# CH32V467WEU-R0.net
KiCad netlist of a schematic drawn in Altium Designer
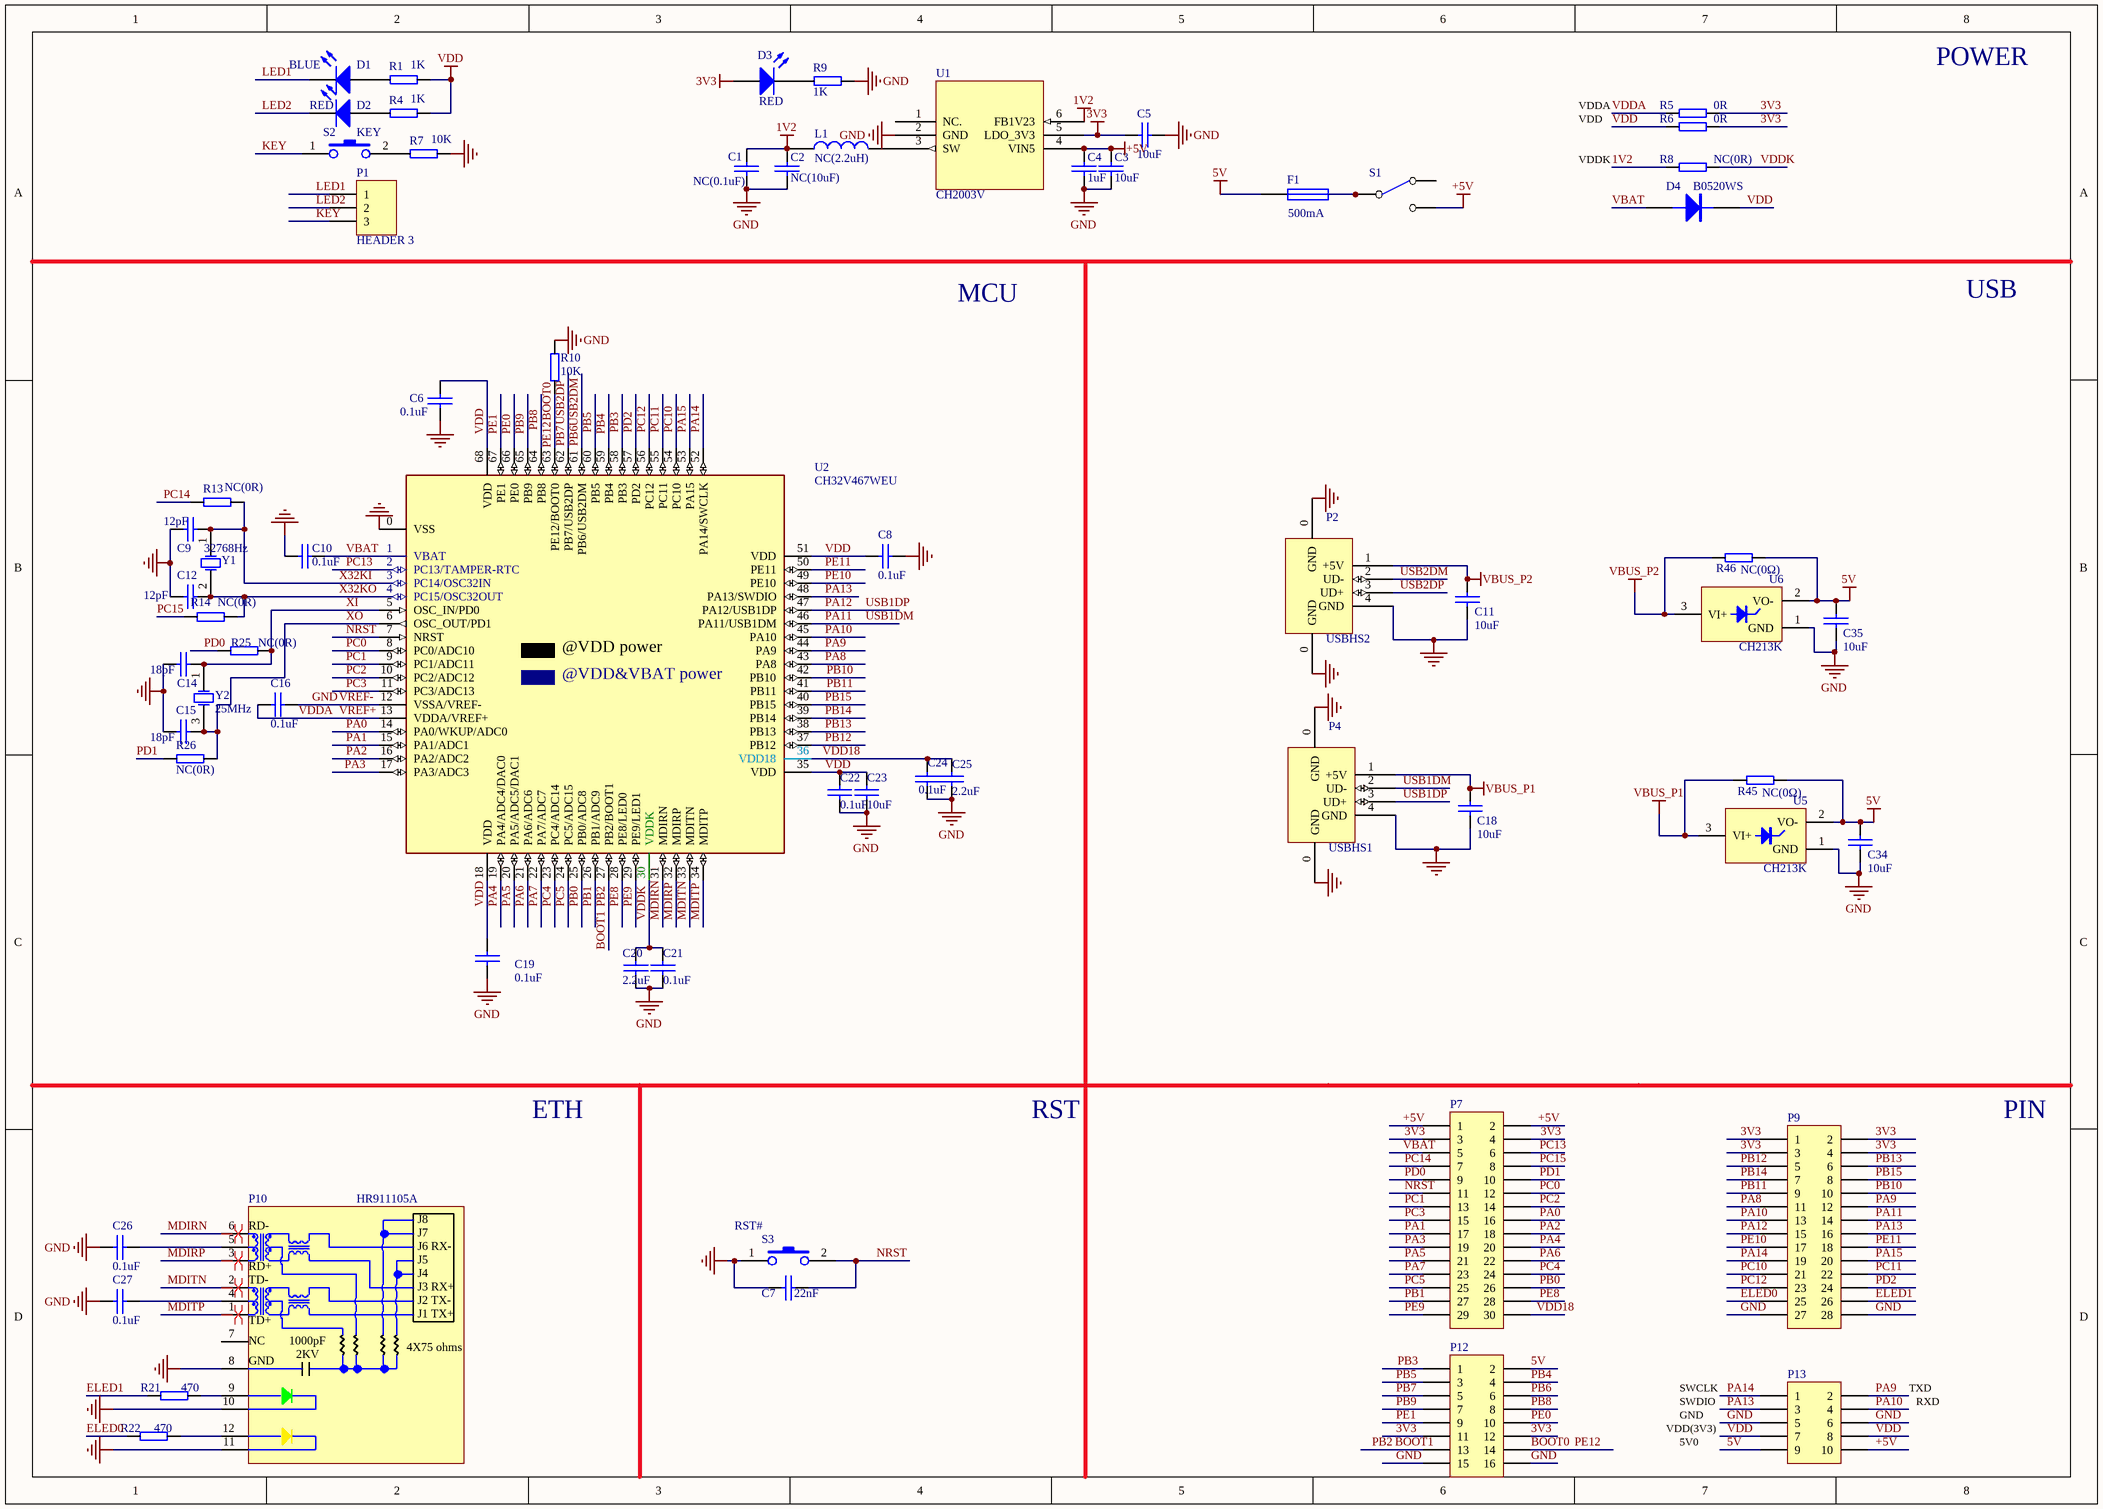
[diagram p0: CH32V467WEU-R0.SchDoc]

(export (version "E")
  (design (tool "Eeschema 10.0.6"))
  (components
    (comp (ref "C1")
      (value "NC(0.1uF)")
      (footprint "0402_C")
      (description "Capacitor")
      (libsource (lib "") (part "CAP_2"))
    )
    (comp (ref "C2")
      (value "NC(10uF)")
      (footprint "0603_C")
      (description "Capacitor")
      (libsource (lib "") (part "CAP_1"))
    )
    (comp (ref "C3")
      (value "10uF")
      (footprint "0603_C")
      (description "Capacitor")
      (libsource (lib "") (part "CAP_1"))
    )
    (comp (ref "C4")
      (value "1uF")
      (footprint "0402_C")
      (description "Capacitor")
      (libsource (lib "") (part "CAP_2"))
    )
    (comp (ref "C5")
      (value "10uF")
      (footprint "0603_C")
      (description "Capacitor")
      (libsource (lib "") (part "CAP_1"))
    )
    (comp (ref "C6")
      (value "0.1uF")
      (footprint "0402_C")
      (description "Capacitor")
      (libsource (lib "") (part "CAP_1"))
    )
    (comp (ref "C7")
      (value "22nF")
      (footprint "0402_C")
      (description "Capacitor")
      (libsource (lib "*") (part "CAP"))
    )
    (comp (ref "C8")
      (value "0.1uF")
      (footprint "0402_C")
      (description "Capacitor")
      (libsource (lib "") (part "CAP_1"))
    )
    (comp (ref "C9")
      (value "12pF")
      (footprint "0402_C")
      (description "Capacitor")
      (libsource (lib "") (part "CAP_1"))
    )
    (comp (ref "C10")
      (value "0.1uF")
      (footprint "0402_C")
      (description "Capacitor")
      (libsource (lib "") (part "CAP_1"))
    )
    (comp (ref "C11")
      (value "10uF")
      (footprint "0603_C")
      (description "Capacitor")
      (libsource (lib "*") (part "CAP"))
    )
    (comp (ref "C12")
      (value "12pF")
      (footprint "0402_C")
      (description "Capacitor")
      (libsource (lib "") (part "CAP_1"))
    )
    (comp (ref "C14")
      (value "18pF")
      (footprint "0402_C")
      (description "Capacitor")
      (libsource (lib "") (part "CAP_1"))
    )
    (comp (ref "C15")
      (value "18pF")
      (footprint "0402_C")
      (description "Capacitor")
      (libsource (lib "") (part "CAP_1"))
    )
    (comp (ref "C16")
      (value "0.1uF")
      (footprint "0402_C")
      (description "Capacitor")
      (libsource (lib "") (part "CAP_1"))
    )
    (comp (ref "C18")
      (value "10uF")
      (footprint "0603_C")
      (description "Capacitor")
      (libsource (lib "*") (part "CAP"))
    )
    (comp (ref "C19")
      (value "0.1uF")
      (footprint "0402_C")
      (description "Capacitor")
      (libsource (lib "") (part "CAP_1"))
    )
    (comp (ref "C20")
      (value "2.2uF")
      (footprint "0402_C")
      (description "Capacitor")
      (libsource (lib "") (part "CAP_1"))
    )
    (comp (ref "C21")
      (value "0.1uF")
      (footprint "0402_C")
      (description "Capacitor")
      (libsource (lib "") (part "CAP_1"))
    )
    (comp (ref "C22")
      (value "0.1uF")
      (footprint "0402_C")
      (description "Capacitor")
      (libsource (lib "") (part "CAP_1"))
    )
    (comp (ref "C23")
      (value "10uF")
      (footprint "0603_C")
      (description "Capacitor")
      (libsource (lib "") (part "CAP_1"))
    )
    (comp (ref "C24")
      (value "0.1uF")
      (footprint "0402_C")
      (description "Capacitor")
      (libsource (lib "") (part "CAP_1"))
    )
    (comp (ref "C25")
      (value "2.2uF")
      (footprint "0402_C")
      (description "Capacitor")
      (libsource (lib "") (part "CAP_1"))
    )
    (comp (ref "C26")
      (value "0.1uF")
      (footprint "0402_C")
      (description "Capacitor")
      (libsource (lib "wch_sch_others") (part "CAP"))
    )
    (comp (ref "C27")
      (value "0.1uF")
      (footprint "0402_C")
      (description "Capacitor")
      (libsource (lib "wch_sch_others") (part "CAP"))
    )
    (comp (ref "C34")
      (value "10uF")
      (footprint "0603_C")
      (description "Capacitor")
      (libsource (lib "*") (part "CAP"))
    )
    (comp (ref "C35")
      (value "10uF")
      (footprint "0603_C")
      (description "Capacitor")
      (libsource (lib "*") (part "CAP"))
    )
    (comp (ref "D1")
      (value "BLUE")
      (footprint "0603+")
      (description "Typical INFRARED GaAs LED")
      (fields (field (name "PUBLISHER") "Altium Limited"))
      (libsource (lib "*") (part "LED0"))
    )
    (comp (ref "D2")
      (value "RED")
      (footprint "0603+")
      (description "Typical INFRARED GaAs LED")
      (fields (field (name "PUBLISHER") "Altium Limited"))
      (libsource (lib "*") (part "LED0"))
    )
    (comp (ref "D3")
      (value "RED")
      (footprint "0603+")
      (description "Typical INFRARED GaAs LED")
      (fields (field (name "PUBLISHER") "Altium Limited"))
      (libsource (lib "*") (part "LED0"))
    )
    (comp (ref "D4")
      (value "B0520WS")
      (footprint "SOD-323")
      (description "Diode")
      (libsource (lib "*") (part "DIODE"))
    )
    (comp (ref "F1")
      (value "500mA")
      (footprint "0603")
      (description "Fuse")
      (libsource (lib "wch_sch_others") (part "FUSE1"))
    )
    (comp (ref "L1") (value "NC(2.2uH)") (footprint "CD32") (libsource (lib "*") (part "INDUCTOR")))
    (comp (ref "P1")
      (value "HEADER 3")
      (footprint "SIP3-2.54MM")
      (description "Header, 3-Pin")
      (libsource (lib "wch_sch_others") (part "HEADER 3"))
    )
    (comp (ref "P2")
      (value "USBHS2")
      (footprint "USBAF")
      (description "USB Port")
      (libsource (lib "*") (part "USB"))
    )
    (comp (ref "P4")
      (value "USBHS1")
      (footprint "USBAF")
      (description "USB Port")
      (libsource (lib "*") (part "USB"))
    )
    (comp (ref "P7")
      (value "HEADER 15x2")
      (footprint "MYPCB:IDC30-2.54MM")
      (description "Header, 15-Pin, Dual row")
      (libsource (lib "wch_sch_others") (part "HEADER 15x2"))
    )
    (comp (ref "P9")
      (value "HEADER 14x2")
      (footprint "MYPCB:IDC28-2.54MM")
      (description "Header, 14-Pin, Dual row")
      (libsource (lib "wch_sch_others") (part "HEADER 14x2"))
    )
    (comp (ref "P10") (value "HR911105A") (footprint "HR911105A") (libsource (lib "*") (part "HR911105A")))
    (comp (ref "P12")
      (value "Ppin")
      (footprint "IDC16-2.54mm")
      (description "Header, 8-Pin, Dual row, Right Angle")
      (fields (field (name "PUBLISHER") "Altium Limited"))
      (libsource (lib "Miscellaneous Connectors") (part "Header 8X2H"))
    )
    (comp (ref "P13")
      (value "LINK")
      (footprint "IDC10-2.54mm")
      (description "Header, 5-Pin, Dual row, Right Angle")
      (fields (field (name "PUBLISHER") "Altium Limited"))
      (libsource (lib "Miscellaneous Connectors") (part "Header 5X2H"))
    )
    (comp (ref "R1") (value "1K") (footprint "0402") (libsource (lib "wch_sch_others") (part "RES")))
    (comp (ref "R4") (value "1K") (footprint "0402") (libsource (lib "wch_sch_others") (part "RES")))
    (comp (ref "R5") (value "0R") (footprint "0402") (libsource (lib "*") (part "R")))
    (comp (ref "R6") (value "0R") (footprint "0402") (libsource (lib "*") (part "R")))
    (comp (ref "R7") (value "10K") (footprint "0402") (libsource (lib "wch_sch_others") (part "RES")))
    (comp (ref "R8") (value "NC(0R)") (footprint "0402") (libsource (lib "*") (part "R")))
    (comp (ref "R9") (value "1K") (footprint "0402") (libsource (lib "wch_sch_others") (part "RES")))
    (comp (ref "R10") (value "10K") (footprint "0402") (libsource (lib "wch_sch_others") (part "RES")))
    (comp (ref "R13") (value "NC(0R)") (footprint "0402") (libsource (lib "wch_sch_others") (part "RES")))
    (comp (ref "R14") (value "NC(0R)") (footprint "0402") (libsource (lib "wch_sch_others") (part "RES")))
    (comp (ref "R21") (value "470") (footprint "0402") (libsource (lib "wch_sch_others") (part "RES")))
    (comp (ref "R22") (value "470") (footprint "0402") (libsource (lib "wch_sch_others") (part "RES")))
    (comp (ref "R25") (value "NC(0R)") (footprint "0402") (libsource (lib "wch_sch_others") (part "RES")))
    (comp (ref "R26") (value "NC(0R)") (footprint "0402") (libsource (lib "wch_sch_others") (part "RES")))
    (comp (ref "R45") (value "NC(0Ω)") (footprint "0402") (libsource (lib "wch_sch_others") (part "RES")))
    (comp (ref "R46") (value "NC(0Ω)") (footprint "0402") (libsource (lib "wch_sch_others") (part "RES")))
    (comp (ref "S1") (value "SW SPDT") (footprint "SW1") (libsource (lib "*") (part "SW SPDT")))
    (comp (ref "S2")
      (value "KEY")
      (footprint "SMD_6.1x3.65x2.5mm-KEY")
      (libsource (lib "wch_sch_others") (part "KEY1"))
    )
    (comp (ref "S3")
      (value "RST#")
      (footprint "SMD_6.1x3.65x2.5mm-KEY")
      (libsource (lib "wch_sch_others") (part "KEY1"))
    )
    (comp (ref "U1")
      (value "CH2003V")
      (footprint "SOT-23-6")
      (description "Step-Down DC-DC Converter, 5V input, 1.23V * 800mA output, with LDO 3.3V * 200mA")
      (libsource (lib "CHXXX") (part "CH2003V"))
    )
    (comp (ref "U2")
      (value "CH32V467WEU")
      (footprint "QFN68_8X8")
      (description "RISC-V FPU HD-MCU, 175MHz, USB_480M, 100M Ethernet & Phy, CAN, ADC, DAC, SRAM")
      (libsource (lib "CHXXX") (part "CH32V467WEU"))
    )
    (comp (ref "U5")
      (value "CH213K")
      (footprint "SOT-23-3")
      (description "Ideal Diode 5V*1A")
      (libsource (lib "*") (part "CH213K"))
    )
    (comp (ref "U6")
      (value "CH213K")
      (footprint "SOT-23-3")
      (description "Ideal Diode 5V*1A")
      (libsource (lib "*") (part "CH213K"))
    )
    (comp (ref "Y1")
      (value "32768Hz")
      (footprint "FC-135")
      (description "Crystal Oscillator")
      (fields (field (name "PUBLISHER") "Altium Limited"))
      (libsource (lib "") (part "XTAL_1"))
    )
    (comp (ref "Y2")
      (value "25MHz")
      (footprint "XT3225")
      (description "Crystal Oscillator")
      (fields (field (name "PUBLISHER") "Altium Limited"))
      (libsource (lib "*") (part "XTAL"))
    )
  )
  (nets
    (net (code "1") (name "+5V") (class "Default")
      (node (ref "C3") (pin "2") (pinfunction "2_2") (pintype "passive"))
      (node (ref "C4") (pin "2") (pinfunction "2_2") (pintype "passive"))
      (node (ref "P13") (pin "10") (pinfunction "10_10") (pintype "passive"))
      (node (ref "P7") (pin "1") (pinfunction "1_1") (pintype "passive"))
      (node (ref "P7") (pin "2") (pinfunction "2_2") (pintype "passive"))
      (node (ref "S1") (pin "2") (pinfunction "NC_2") (pintype "passive"))
      (node (ref "U1") (pin "4") (pinfunction "VIN5_4") (pintype "power_in"))
    )
    (net (code "3") (name "/BOOT0") (class "Default")
      (node (ref "P12") (pin "14") (pinfunction "14_14") (pintype "passive"))
      (node (ref "R10") (pin "2") (pintype "passive"))
      (node (ref "U2") (pin "63") (pinfunction "PE12/BOOT0_63") (pintype "bidirectional"))
    )
    (net (code "4") (name "/BOOT1") (class "Default")
      (node (ref "P12") (pin "13") (pinfunction "13_13") (pintype "passive"))
      (node (ref "U2") (pin "27") (pinfunction "PB2/BOOT1_27") (pintype "bidirectional"))
    )
    (net (code "5") (name "/ELED0") (class "Default")
      (node (ref "P9") (pin "25") (pinfunction "25_25") (pintype "passive"))
      (node (ref "R22") (pin "1") (pintype "passive"))
    )
    (net (code "6") (name "/ELED1") (class "Default")
      (node (ref "P9") (pin "26") (pinfunction "26_26") (pintype "passive"))
      (node (ref "R21") (pin "1") (pintype "passive"))
    )
    (net (code "7") (name "/KEY") (class "Default")
      (node (ref "P1") (pin "3") (pinfunction "3_3") (pintype "passive"))
      (node (ref "S2") (pin "1") (pinfunction "1_1") (pintype "passive"))
    )
    (net (code "8") (name "/LED1") (class "Default")
      (node (ref "D1") (pin "2") (pinfunction "K_2") (pintype "passive"))
      (node (ref "P1") (pin "1") (pinfunction "1_1") (pintype "passive"))
    )
    (net (code "9") (name "/LED2") (class "Default")
      (node (ref "D2") (pin "2") (pinfunction "K_2") (pintype "passive"))
      (node (ref "P1") (pin "2") (pinfunction "2_2") (pintype "passive"))
    )
    (net (code "10") (name "/MDIRN") (class "Default")
      (node (ref "P10") (pin "6") (pintype "passive"))
      (node (ref "U2") (pin "31") (pinfunction "MDIRN_31") (pintype "bidirectional"))
    )
    (net (code "11") (name "/MDIRP") (class "Default")
      (node (ref "P10") (pin "3") (pintype "passive"))
      (node (ref "U2") (pin "32") (pinfunction "MDIRP_32") (pintype "bidirectional"))
    )
    (net (code "12") (name "/MDITN") (class "Default")
      (node (ref "P10") (pin "2") (pintype "passive"))
      (node (ref "U2") (pin "33") (pinfunction "MDITN_33") (pintype "bidirectional"))
    )
    (net (code "13") (name "/MDITP") (class "Default")
      (node (ref "P10") (pin "1") (pintype "passive"))
      (node (ref "U2") (pin "34") (pinfunction "MDITP_34") (pintype "bidirectional"))
    )
    (net (code "14") (name "/NRST") (class "Default")
      (node (ref "C7") (pin "2") (pinfunction "2_2") (pintype "passive"))
      (node (ref "P7") (pin "11") (pinfunction "11_11") (pintype "passive"))
      (node (ref "S3") (pin "2") (pinfunction "2_2") (pintype "passive"))
      (node (ref "U2") (pin "7") (pinfunction "NRST_7") (pintype "input"))
    )
    (net (code "15") (name "/PA0") (class "Default")
      (node (ref "P7") (pin "16") (pinfunction "16_16") (pintype "passive"))
      (node (ref "U2") (pin "14") (pinfunction "PA0/WKUP/ADC0_14") (pintype "bidirectional"))
    )
    (net (code "16") (name "/PA1") (class "Default")
      (node (ref "P7") (pin "17") (pinfunction "17_17") (pintype "passive"))
      (node (ref "U2") (pin "15") (pinfunction "PA1/ADC1_15") (pintype "bidirectional"))
    )
    (net (code "17") (name "/PA2") (class "Default")
      (node (ref "P7") (pin "18") (pinfunction "18_18") (pintype "passive"))
      (node (ref "U2") (pin "16") (pinfunction "PA2/ADC2_16") (pintype "bidirectional"))
    )
    (net (code "18") (name "/PA3") (class "Default")
      (node (ref "P7") (pin "19") (pinfunction "19_19") (pintype "passive"))
      (node (ref "U2") (pin "17") (pinfunction "PA3/ADC3_17") (pintype "bidirectional"))
    )
    (net (code "19") (name "/PA4") (class "Default")
      (node (ref "P7") (pin "20") (pinfunction "20_20") (pintype "passive"))
      (node (ref "U2") (pin "19") (pinfunction "PA4/ADC4/DAC0_19") (pintype "bidirectional"))
    )
    (net (code "20") (name "/PA5") (class "Default")
      (node (ref "P7") (pin "21") (pinfunction "21_21") (pintype "passive"))
      (node (ref "U2") (pin "20") (pinfunction "PA5/ADC5/DAC1_20") (pintype "bidirectional"))
    )
    (net (code "21") (name "/PA6") (class "Default")
      (node (ref "P7") (pin "22") (pinfunction "22_22") (pintype "passive"))
      (node (ref "U2") (pin "21") (pinfunction "PA6/ADC6_21") (pintype "bidirectional"))
    )
    (net (code "22") (name "/PA7") (class "Default")
      (node (ref "P7") (pin "23") (pinfunction "23_23") (pintype "passive"))
      (node (ref "U2") (pin "22") (pinfunction "PA7/ADC7_22") (pintype "bidirectional"))
    )
    (net (code "23") (name "/PA8") (class "Default")
      (node (ref "P9") (pin "11") (pinfunction "11_11") (pintype "passive"))
      (node (ref "U2") (pin "43") (pinfunction "PA8_43") (pintype "bidirectional"))
    )
    (net (code "24") (name "/PA9") (class "Default")
      (node (ref "P13") (pin "2") (pinfunction "2_2") (pintype "passive"))
      (node (ref "P9") (pin "12") (pinfunction "12_12") (pintype "passive"))
      (node (ref "U2") (pin "44") (pinfunction "PA9_44") (pintype "bidirectional"))
    )
    (net (code "25") (name "/PA10") (class "Default")
      (node (ref "P13") (pin "4") (pinfunction "4_4") (pintype "passive"))
      (node (ref "P9") (pin "13") (pinfunction "13_13") (pintype "passive"))
      (node (ref "U2") (pin "45") (pinfunction "PA10_45") (pintype "bidirectional"))
    )
    (net (code "26") (name "/PA11") (class "Default")
      (node (ref "P4") (pin "2") (pinfunction "UD-_2") (pintype "bidirectional"))
      (node (ref "P9") (pin "14") (pinfunction "14_14") (pintype "passive"))
      (node (ref "U2") (pin "46") (pinfunction "PA11/USB1DM_46") (pintype "bidirectional"))
    )
    (net (code "27") (name "/PA12") (class "Default")
      (node (ref "P4") (pin "3") (pinfunction "UD+_3") (pintype "bidirectional"))
      (node (ref "P9") (pin "15") (pinfunction "15_15") (pintype "passive"))
      (node (ref "U2") (pin "47") (pinfunction "PA12/USB1DP_47") (pintype "bidirectional"))
    )
    (net (code "28") (name "/PA13") (class "Default")
      (node (ref "P13") (pin "3") (pinfunction "3_3") (pintype "passive"))
      (node (ref "P9") (pin "16") (pinfunction "16_16") (pintype "passive"))
      (node (ref "U2") (pin "48") (pinfunction "PA13/SWDIO_48") (pintype "bidirectional"))
    )
    (net (code "29") (name "/PA14") (class "Default")
      (node (ref "P13") (pin "1") (pinfunction "1_1") (pintype "passive"))
      (node (ref "P9") (pin "19") (pinfunction "19_19") (pintype "passive"))
      (node (ref "U2") (pin "52") (pinfunction "PA14/SWCLK_52") (pintype "bidirectional"))
    )
    (net (code "30") (name "/PA15") (class "Default")
      (node (ref "P9") (pin "20") (pinfunction "20_20") (pintype "passive"))
      (node (ref "U2") (pin "53") (pinfunction "PA15_53") (pintype "bidirectional"))
    )
    (net (code "31") (name "/PB0") (class "Default")
      (node (ref "P7") (pin "26") (pinfunction "26_26") (pintype "passive"))
      (node (ref "U2") (pin "25") (pinfunction "PB0/ADC8_25") (pintype "bidirectional"))
    )
    (net (code "32") (name "/PB1") (class "Default")
      (node (ref "P7") (pin "27") (pinfunction "27_27") (pintype "passive"))
      (node (ref "U2") (pin "26") (pinfunction "PB1/ADC9_26") (pintype "bidirectional"))
    )
    (net (code "33") (name "/PB3") (class "Default")
      (node (ref "P12") (pin "1") (pinfunction "1_1") (pintype "passive"))
      (node (ref "U2") (pin "58") (pinfunction "PB3_58") (pintype "bidirectional"))
    )
    (net (code "34") (name "/PB4") (class "Default")
      (node (ref "P12") (pin "4") (pinfunction "4_4") (pintype "passive"))
      (node (ref "U2") (pin "59") (pinfunction "PB4_59") (pintype "bidirectional"))
    )
    (net (code "35") (name "/PB5") (class "Default")
      (node (ref "P12") (pin "3") (pinfunction "3_3") (pintype "passive"))
      (node (ref "U2") (pin "60") (pinfunction "PB5_60") (pintype "bidirectional"))
    )
    (net (code "36") (name "/PB6") (class "Default")
      (node (ref "P12") (pin "6") (pinfunction "6_6") (pintype "passive"))
      (node (ref "P2") (pin "2") (pinfunction "UD-_2") (pintype "bidirectional"))
      (node (ref "U2") (pin "61") (pinfunction "PB6/USB2DM_61") (pintype "bidirectional"))
    )
    (net (code "37") (name "/PB7") (class "Default")
      (node (ref "P12") (pin "5") (pinfunction "5_5") (pintype "passive"))
      (node (ref "P2") (pin "3") (pinfunction "UD+_3") (pintype "bidirectional"))
      (node (ref "U2") (pin "62") (pinfunction "PB7/USB2DP_62") (pintype "bidirectional"))
    )
    (net (code "38") (name "/PB8") (class "Default")
      (node (ref "P12") (pin "8") (pinfunction "8_8") (pintype "passive"))
      (node (ref "U2") (pin "64") (pinfunction "PB8_64") (pintype "bidirectional"))
    )
    (net (code "39") (name "/PB9") (class "Default")
      (node (ref "P12") (pin "7") (pinfunction "7_7") (pintype "passive"))
      (node (ref "U2") (pin "65") (pinfunction "PB9_65") (pintype "bidirectional"))
    )
    (net (code "40") (name "/PB10") (class "Default")
      (node (ref "P9") (pin "10") (pinfunction "10_10") (pintype "passive"))
      (node (ref "U2") (pin "42") (pinfunction "PB10_42") (pintype "bidirectional"))
    )
    (net (code "41") (name "/PB11") (class "Default")
      (node (ref "P9") (pin "9") (pinfunction "9_9") (pintype "passive"))
      (node (ref "U2") (pin "41") (pinfunction "PB11_41") (pintype "bidirectional"))
    )
    (net (code "42") (name "/PB12") (class "Default")
      (node (ref "P9") (pin "5") (pinfunction "5_5") (pintype "passive"))
      (node (ref "U2") (pin "37") (pinfunction "PB12_37") (pintype "bidirectional"))
    )
    (net (code "43") (name "/PB13") (class "Default")
      (node (ref "P9") (pin "6") (pinfunction "6_6") (pintype "passive"))
      (node (ref "U2") (pin "38") (pinfunction "PB13_38") (pintype "bidirectional"))
    )
    (net (code "44") (name "/PB14") (class "Default")
      (node (ref "P9") (pin "7") (pinfunction "7_7") (pintype "passive"))
      (node (ref "U2") (pin "39") (pinfunction "PB14_39") (pintype "bidirectional"))
    )
    (net (code "45") (name "/PB15") (class "Default")
      (node (ref "P9") (pin "8") (pinfunction "8_8") (pintype "passive"))
      (node (ref "U2") (pin "40") (pinfunction "PB15_40") (pintype "bidirectional"))
    )
    (net (code "46") (name "/PC0") (class "Default")
      (node (ref "P7") (pin "12") (pinfunction "12_12") (pintype "passive"))
      (node (ref "U2") (pin "8") (pinfunction "PC0/ADC10_8") (pintype "bidirectional"))
    )
    (net (code "47") (name "/PC1") (class "Default")
      (node (ref "P7") (pin "13") (pinfunction "13_13") (pintype "passive"))
      (node (ref "U2") (pin "9") (pinfunction "PC1/ADC11_9") (pintype "bidirectional"))
    )
    (net (code "48") (name "/PC2") (class "Default")
      (node (ref "P7") (pin "14") (pinfunction "14_14") (pintype "passive"))
      (node (ref "U2") (pin "10") (pinfunction "PC2/ADC12_10") (pintype "bidirectional"))
    )
    (net (code "49") (name "/PC3") (class "Default")
      (node (ref "P7") (pin "15") (pinfunction "15_15") (pintype "passive"))
      (node (ref "U2") (pin "11") (pinfunction "PC3/ADC13_11") (pintype "bidirectional"))
    )
    (net (code "50") (name "/PC4") (class "Default")
      (node (ref "P7") (pin "24") (pinfunction "24_24") (pintype "passive"))
      (node (ref "U2") (pin "23") (pinfunction "PC4/ADC14_23") (pintype "bidirectional"))
    )
    (net (code "51") (name "/PC5") (class "Default")
      (node (ref "P7") (pin "25") (pinfunction "25_25") (pintype "passive"))
      (node (ref "U2") (pin "24") (pinfunction "PC5/ADC15_24") (pintype "bidirectional"))
    )
    (net (code "52") (name "/PC10") (class "Default")
      (node (ref "P9") (pin "21") (pinfunction "21_21") (pintype "passive"))
      (node (ref "U2") (pin "54") (pinfunction "PC10_54") (pintype "bidirectional"))
    )
    (net (code "53") (name "/PC11") (class "Default")
      (node (ref "P9") (pin "22") (pinfunction "22_22") (pintype "passive"))
      (node (ref "U2") (pin "55") (pinfunction "PC11_55") (pintype "bidirectional"))
    )
    (net (code "54") (name "/PC12") (class "Default")
      (node (ref "P9") (pin "23") (pinfunction "23_23") (pintype "passive"))
      (node (ref "U2") (pin "56") (pinfunction "PC12_56") (pintype "bidirectional"))
    )
    (net (code "55") (name "/PC13") (class "Default")
      (node (ref "P7") (pin "6") (pinfunction "6_6") (pintype "passive"))
      (node (ref "U2") (pin "2") (pinfunction "PC13/TAMPER-RTC_2") (pintype "bidirectional"))
    )
    (net (code "56") (name "/PC14") (class "Default")
      (node (ref "P7") (pin "7") (pinfunction "7_7") (pintype "passive"))
      (node (ref "R13") (pin "1") (pintype "passive"))
    )
    (net (code "57") (name "/PC15") (class "Default")
      (node (ref "P7") (pin "8") (pinfunction "8_8") (pintype "passive"))
      (node (ref "R14") (pin "1") (pintype "passive"))
    )
    (net (code "58") (name "/PD0") (class "Default")
      (node (ref "P7") (pin "9") (pinfunction "9_9") (pintype "passive"))
      (node (ref "R25") (pin "1") (pintype "passive"))
    )
    (net (code "59") (name "/PD1") (class "Default")
      (node (ref "P7") (pin "10") (pinfunction "10_10") (pintype "passive"))
      (node (ref "R26") (pin "2") (pintype "passive"))
    )
    (net (code "60") (name "/PD2") (class "Default")
      (node (ref "P9") (pin "24") (pinfunction "24_24") (pintype "passive"))
      (node (ref "U2") (pin "57") (pinfunction "PD2_57") (pintype "bidirectional"))
    )
    (net (code "61") (name "/PE0") (class "Default")
      (node (ref "P12") (pin "10") (pinfunction "10_10") (pintype "passive"))
      (node (ref "U2") (pin "66") (pinfunction "PE0_66") (pintype "bidirectional"))
    )
    (net (code "62") (name "/PE1") (class "Default")
      (node (ref "P12") (pin "9") (pinfunction "9_9") (pintype "passive"))
      (node (ref "U2") (pin "67") (pinfunction "PE1_67") (pintype "bidirectional"))
    )
    (net (code "63") (name "/PE8") (class "Default")
      (node (ref "P7") (pin "28") (pinfunction "28_28") (pintype "passive"))
      (node (ref "U2") (pin "28") (pinfunction "PE8/LED0_28") (pintype "bidirectional"))
    )
    (net (code "64") (name "/PE9") (class "Default")
      (node (ref "P7") (pin "29") (pinfunction "29_29") (pintype "passive"))
      (node (ref "U2") (pin "29") (pinfunction "PE9/LED1_29") (pintype "bidirectional"))
    )
    (net (code "65") (name "/PE10") (class "Default")
      (node (ref "P9") (pin "17") (pinfunction "17_17") (pintype "passive"))
      (node (ref "U2") (pin "49") (pinfunction "PE10_49") (pintype "bidirectional"))
    )
    (net (code "66") (name "/PE11") (class "Default")
      (node (ref "P9") (pin "18") (pinfunction "18_18") (pintype "passive"))
      (node (ref "U2") (pin "50") (pinfunction "PE11_50") (pintype "bidirectional"))
    )
    (net (code "67") (name "/VBAT") (class "Default")
      (node (ref "C10") (pin "2") (pinfunction "2_2") (pintype "passive"))
      (node (ref "D4") (pin "1") (pinfunction "A_1") (pintype "passive"))
      (node (ref "P7") (pin "5") (pinfunction "5_5") (pintype "passive"))
      (node (ref "U2") (pin "1") (pinfunction "VBAT_1") (pintype "power_in"))
    )
    (net (code "68") (name "/VDD18") (class "Default")
      (node (ref "C24") (pin "2") (pinfunction "2_2") (pintype "passive"))
      (node (ref "C25") (pin "2") (pinfunction "2_2") (pintype "passive"))
      (node (ref "P7") (pin "30") (pinfunction "30_30") (pintype "passive"))
      (node (ref "U2") (pin "36") (pinfunction "VDD18_36") (pintype "power_in"))
    )
    (net (code "69") (name "/VDDA") (class "Default")
      (node (ref "C16") (pin "1") (pinfunction "1_1") (pintype "passive"))
      (node (ref "R5") (pin "2") (pinfunction "2_2") (pintype "passive"))
      (node (ref "U2") (pin "13") (pinfunction "VDDA/VREF+_13") (pintype "power_in"))
    )
    (net (code "70") (name "/VDDK") (class "Default")
      (node (ref "C20") (pin "2") (pinfunction "2_2") (pintype "passive"))
      (node (ref "C21") (pin "2") (pinfunction "2_2") (pintype "passive"))
      (node (ref "R8") (pin "1") (pinfunction "1_1") (pintype "passive"))
      (node (ref "U2") (pin "30") (pinfunction "VDDK_30") (pintype "power_in"))
    )
    (net (code "71") (name "/X32KI") (class "Default")
      (node (ref "C9") (pin "2") (pinfunction "2_2") (pintype "passive"))
      (node (ref "R13") (pin "2") (pintype "passive"))
      (node (ref "U2") (pin "3") (pinfunction "PC14/OSC32IN_3") (pintype "bidirectional"))
      (node (ref "Y1") (pin "1") (pinfunction "OSC1_1") (pintype "passive"))
    )
    (net (code "72") (name "/X32KO") (class "Default")
      (node (ref "C12") (pin "2") (pinfunction "2_2") (pintype "passive"))
      (node (ref "R14") (pin "2") (pintype "passive"))
      (node (ref "U2") (pin "4") (pinfunction "PC15/OSC32OUT_4") (pintype "bidirectional"))
      (node (ref "Y1") (pin "2") (pinfunction "OSC2_2") (pintype "passive"))
    )
    (net (code "73") (name "/XI") (class "Default")
      (node (ref "C14") (pin "2") (pinfunction "2_2") (pintype "passive"))
      (node (ref "R25") (pin "2") (pintype "passive"))
      (node (ref "U2") (pin "5") (pinfunction "OSC_IN/PD0_5") (pintype "input"))
      (node (ref "Y2") (pin "1") (pinfunction "OSC1_1") (pintype "passive"))
    )
    (net (code "74") (name "/XO") (class "Default")
      (node (ref "C15") (pin "2") (pinfunction "2_2") (pintype "passive"))
      (node (ref "R26") (pin "1") (pintype "passive"))
      (node (ref "U2") (pin "6") (pinfunction "OSC_OUT/PD1_6") (pintype "output"))
      (node (ref "Y2") (pin "3") (pinfunction "OSC2_3") (pintype "passive"))
    )
    (net (code "75") (name "1V2") (class "Default")
      (node (ref "C1") (pin "2") (pinfunction "2_2") (pintype "passive"))
      (node (ref "C2") (pin "2") (pinfunction "2_2") (pintype "passive"))
      (node (ref "L1") (pin "2") (pinfunction "2_2") (pintype "passive"))
      (node (ref "R8") (pin "2") (pinfunction "2_2") (pintype "passive"))
      (node (ref "U1") (pin "6") (pinfunction "FB1V23_6") (pintype "input"))
    )
    (net (code "76") (name "3V3") (class "Default")
      (node (ref "C5") (pin "2") (pinfunction "2_2") (pintype "passive"))
      (node (ref "D3") (pin "1") (pinfunction "A_1") (pintype "passive"))
      (node (ref "P12") (pin "11") (pinfunction "11_11") (pintype "passive"))
      (node (ref "P12") (pin "12") (pinfunction "12_12") (pintype "passive"))
      (node (ref "P7") (pin "3") (pinfunction "3_3") (pintype "passive"))
      (node (ref "P7") (pin "4") (pinfunction "4_4") (pintype "passive"))
      (node (ref "P9") (pin "1") (pinfunction "1_1") (pintype "passive"))
      (node (ref "P9") (pin "2") (pinfunction "2_2") (pintype "passive"))
      (node (ref "P9") (pin "3") (pinfunction "3_3") (pintype "passive"))
      (node (ref "P9") (pin "4") (pinfunction "4_4") (pintype "passive"))
      (node (ref "R5") (pin "1") (pinfunction "1_1") (pintype "passive"))
      (node (ref "R6") (pin "1") (pinfunction "1_1") (pintype "passive"))
      (node (ref "U1") (pin "5") (pinfunction "LDO_3V3_5") (pintype "power_in"))
    )
    (net (code "77") (name "5V") (class "Default")
      (node (ref "C34") (pin "1") (pinfunction "1_1") (pintype "passive"))
      (node (ref "C35") (pin "1") (pinfunction "1_1") (pintype "passive"))
      (node (ref "F1") (pin "1") (pinfunction "1_1") (pintype "passive"))
      (node (ref "P12") (pin "2") (pinfunction "2_2") (pintype "passive"))
      (node (ref "P13") (pin "9") (pinfunction "9_9") (pintype "passive"))
      (node (ref "R45") (pin "1") (pintype "passive"))
      (node (ref "R46") (pin "1") (pintype "passive"))
      (node (ref "U5") (pin "2") (pinfunction "VO-_2") (pintype "power_in"))
      (node (ref "U6") (pin "2") (pinfunction "VO-_2") (pintype "power_in"))
    )
    (net (code "78") (name "GND") (class "Default")
      (node (ref "C1") (pin "1") (pinfunction "1_1") (pintype "passive"))
      (node (ref "C10") (pin "1") (pinfunction "1_1") (pintype "passive"))
      (node (ref "C11") (pin "2") (pinfunction "2_2") (pintype "passive"))
      (node (ref "C12") (pin "1") (pinfunction "1_1") (pintype "passive"))
      (node (ref "C14") (pin "1") (pinfunction "1_1") (pintype "passive"))
      (node (ref "C15") (pin "1") (pinfunction "1_1") (pintype "passive"))
      (node (ref "C16") (pin "2") (pinfunction "2_2") (pintype "passive"))
      (node (ref "C18") (pin "2") (pinfunction "2_2") (pintype "passive"))
      (node (ref "C19") (pin "1") (pinfunction "1_1") (pintype "passive"))
      (node (ref "C2") (pin "1") (pinfunction "1_1") (pintype "passive"))
      (node (ref "C20") (pin "1") (pinfunction "1_1") (pintype "passive"))
      (node (ref "C21") (pin "1") (pinfunction "1_1") (pintype "passive"))
      (node (ref "C22") (pin "1") (pinfunction "1_1") (pintype "passive"))
      (node (ref "C23") (pin "1") (pinfunction "1_1") (pintype "passive"))
      (node (ref "C24") (pin "1") (pinfunction "1_1") (pintype "passive"))
      (node (ref "C25") (pin "1") (pinfunction "1_1") (pintype "passive"))
      (node (ref "C26") (pin "1") (pinfunction "1_1") (pintype "passive"))
      (node (ref "C27") (pin "1") (pinfunction "1_1") (pintype "passive"))
      (node (ref "C3") (pin "1") (pinfunction "1_1") (pintype "passive"))
      (node (ref "C34") (pin "2") (pinfunction "2_2") (pintype "passive"))
      (node (ref "C35") (pin "2") (pinfunction "2_2") (pintype "passive"))
      (node (ref "C4") (pin "1") (pinfunction "1_1") (pintype "passive"))
      (node (ref "C5") (pin "1") (pinfunction "1_1") (pintype "passive"))
      (node (ref "C6") (pin "1") (pinfunction "1_1") (pintype "passive"))
      (node (ref "C7") (pin "1") (pinfunction "1_1") (pintype "passive"))
      (node (ref "C8") (pin "2") (pinfunction "2_2") (pintype "passive"))
      (node (ref "C9") (pin "1") (pinfunction "1_1") (pintype "passive"))
      (node (ref "P10") (pin "10") (pintype "passive"))
      (node (ref "P10") (pin "11") (pintype "passive"))
      (node (ref "P10") (pin "8") (pintype "passive"))
      (node (ref "P12") (pin "15") (pinfunction "15_15") (pintype "passive"))
      (node (ref "P12") (pin "16") (pinfunction "16_16") (pintype "passive"))
      (node (ref "P13") (pin "5") (pinfunction "5_5") (pintype "passive"))
      (node (ref "P13") (pin "6") (pinfunction "6_6") (pintype "passive"))
      (node (ref "P2") (pin "0") (pinfunction "GND_0") (pintype "power_in"))
      (node (ref "P2") (pin "4") (pinfunction "GND_4") (pintype "power_in"))
      (node (ref "P4") (pin "0") (pinfunction "GND_0") (pintype "power_in"))
      (node (ref "P4") (pin "4") (pinfunction "GND_4") (pintype "power_in"))
      (node (ref "P9") (pin "27") (pinfunction "27_27") (pintype "passive"))
      (node (ref "P9") (pin "28") (pinfunction "28_28") (pintype "passive"))
      (node (ref "R10") (pin "1") (pintype "passive"))
      (node (ref "R7") (pin "1") (pintype "passive"))
      (node (ref "R9") (pin "2") (pintype "passive"))
      (node (ref "S3") (pin "1") (pinfunction "1_1") (pintype "passive"))
      (node (ref "U1") (pin "2") (pinfunction "GND_2") (pintype "power_in"))
      (node (ref "U2") (pin "0") (pinfunction "VSS_0") (pintype "power_in"))
      (node (ref "U2") (pin "12") (pinfunction "VSSA/VREF-_12") (pintype "power_in"))
      (node (ref "U5") (pin "1") (pinfunction "GND_1") (pintype "power_in"))
      (node (ref "U6") (pin "1") (pinfunction "GND_1") (pintype "power_in"))
    )
    (net (code "79") (name "Net-(C26-Pad2)") (class "Default")
      (node (ref "C26") (pin "2") (pinfunction "2_2") (pintype "passive"))
      (node (ref "P10") (pin "5") (pintype "passive"))
    )
    (net (code "80") (name "Net-(C27-Pad2)") (class "Default")
      (node (ref "C27") (pin "2") (pinfunction "2_2") (pintype "passive"))
      (node (ref "P10") (pin "4") (pintype "passive"))
    )
    (net (code "81") (name "Net-(D1-A)") (class "Default")
      (node (ref "D1") (pin "1") (pinfunction "A_1") (pintype "passive"))
      (node (ref "R1") (pin "2") (pintype "passive"))
    )
    (net (code "82") (name "Net-(D2-A)") (class "Default")
      (node (ref "D2") (pin "1") (pinfunction "A_1") (pintype "passive"))
      (node (ref "R4") (pin "2") (pintype "passive"))
    )
    (net (code "83") (name "Net-(D3-K)") (class "Default")
      (node (ref "D3") (pin "2") (pinfunction "K_2") (pintype "passive"))
      (node (ref "R9") (pin "1") (pintype "passive"))
    )
    (net (code "84") (name "Net-(P10-Pad9)") (class "Default")
      (node (ref "P10") (pin "9") (pintype "passive"))
      (node (ref "R21") (pin "2") (pintype "passive"))
    )
    (net (code "85") (name "Net-(P10-Pad12)") (class "Default")
      (node (ref "P10") (pin "12") (pintype "passive"))
      (node (ref "R22") (pin "2") (pintype "passive"))
    )
    (net (code "86") (name "Net-(R7-Pad2)") (class "Default")
      (node (ref "R7") (pin "2") (pintype "passive"))
      (node (ref "S2") (pin "2") (pinfunction "2_2") (pintype "passive"))
    )
    (net (code "87") (name "Net-(S1-COMMON)") (class "Default")
      (node (ref "F1") (pin "2") (pinfunction "2_2") (pintype "passive"))
      (node (ref "S1") (pin "1") (pinfunction "COMMON_1") (pintype "passive"))
    )
    (net (code "88") (name "Net-(U1-SW)") (class "Default")
      (node (ref "L1") (pin "1") (pinfunction "1_1") (pintype "passive"))
      (node (ref "U1") (pin "3") (pinfunction "SW_3") (pintype "output"))
    )
    (net (code "89") (name "VBUS_P1") (class "Default")
      (node (ref "C18") (pin "1") (pinfunction "1_1") (pintype "passive"))
      (node (ref "P4") (pin "1") (pinfunction "+5V_1") (pintype "power_in"))
      (node (ref "R45") (pin "2") (pintype "passive"))
      (node (ref "U5") (pin "3") (pinfunction "VI+_3") (pintype "power_in"))
    )
    (net (code "90") (name "VBUS_P2") (class "Default")
      (node (ref "C11") (pin "1") (pinfunction "1_1") (pintype "passive"))
      (node (ref "P2") (pin "1") (pinfunction "+5V_1") (pintype "power_in"))
      (node (ref "R46") (pin "2") (pintype "passive"))
      (node (ref "U6") (pin "3") (pinfunction "VI+_3") (pintype "power_in"))
    )
    (net (code "91") (name "VDD") (class "Default")
      (node (ref "C19") (pin "2") (pinfunction "2_2") (pintype "passive"))
      (node (ref "C22") (pin "2") (pinfunction "2_2") (pintype "passive"))
      (node (ref "C23") (pin "2") (pinfunction "2_2") (pintype "passive"))
      (node (ref "C6") (pin "2") (pinfunction "2_2") (pintype "passive"))
      (node (ref "C8") (pin "1") (pinfunction "1_1") (pintype "passive"))
      (node (ref "D4") (pin "2") (pinfunction "K_2") (pintype "passive"))
      (node (ref "P13") (pin "7") (pinfunction "7_7") (pintype "passive"))
      (node (ref "P13") (pin "8") (pinfunction "8_8") (pintype "passive"))
      (node (ref "R1") (pin "1") (pintype "passive"))
      (node (ref "R4") (pin "1") (pintype "passive"))
      (node (ref "R6") (pin "2") (pinfunction "2_2") (pintype "passive"))
      (node (ref "U2") (pin "18") (pinfunction "VDD_18") (pintype "power_in"))
      (node (ref "U2") (pin "35") (pinfunction "VDD_35") (pintype "power_in"))
      (node (ref "U2") (pin "51") (pinfunction "VDD_51") (pintype "power_in"))
      (node (ref "U2") (pin "68") (pinfunction "VDD_68") (pintype "power_in"))
    )
    (net (code "92") (name "unconnected-(P10-Pad7)") (class "Default")
      (node (ref "P10") (pin "7") (pintype "passive"))
    )
    (net (code "93") (name "unconnected-(S1-NO-Pad3)") (class "Default")
      (node (ref "S1") (pin "3") (pinfunction "NO_3") (pintype "passive"))
    )
    (net (code "94") (name "unconnected-(U1-NC.-Pad1)") (class "Default")
      (node (ref "U1") (pin "1") (pinfunction "NC._1") (pintype "passive"))
    )
  )
)
